# Receiver_SMD.net
KiCad netlist of a schematic drawn in EAGLE
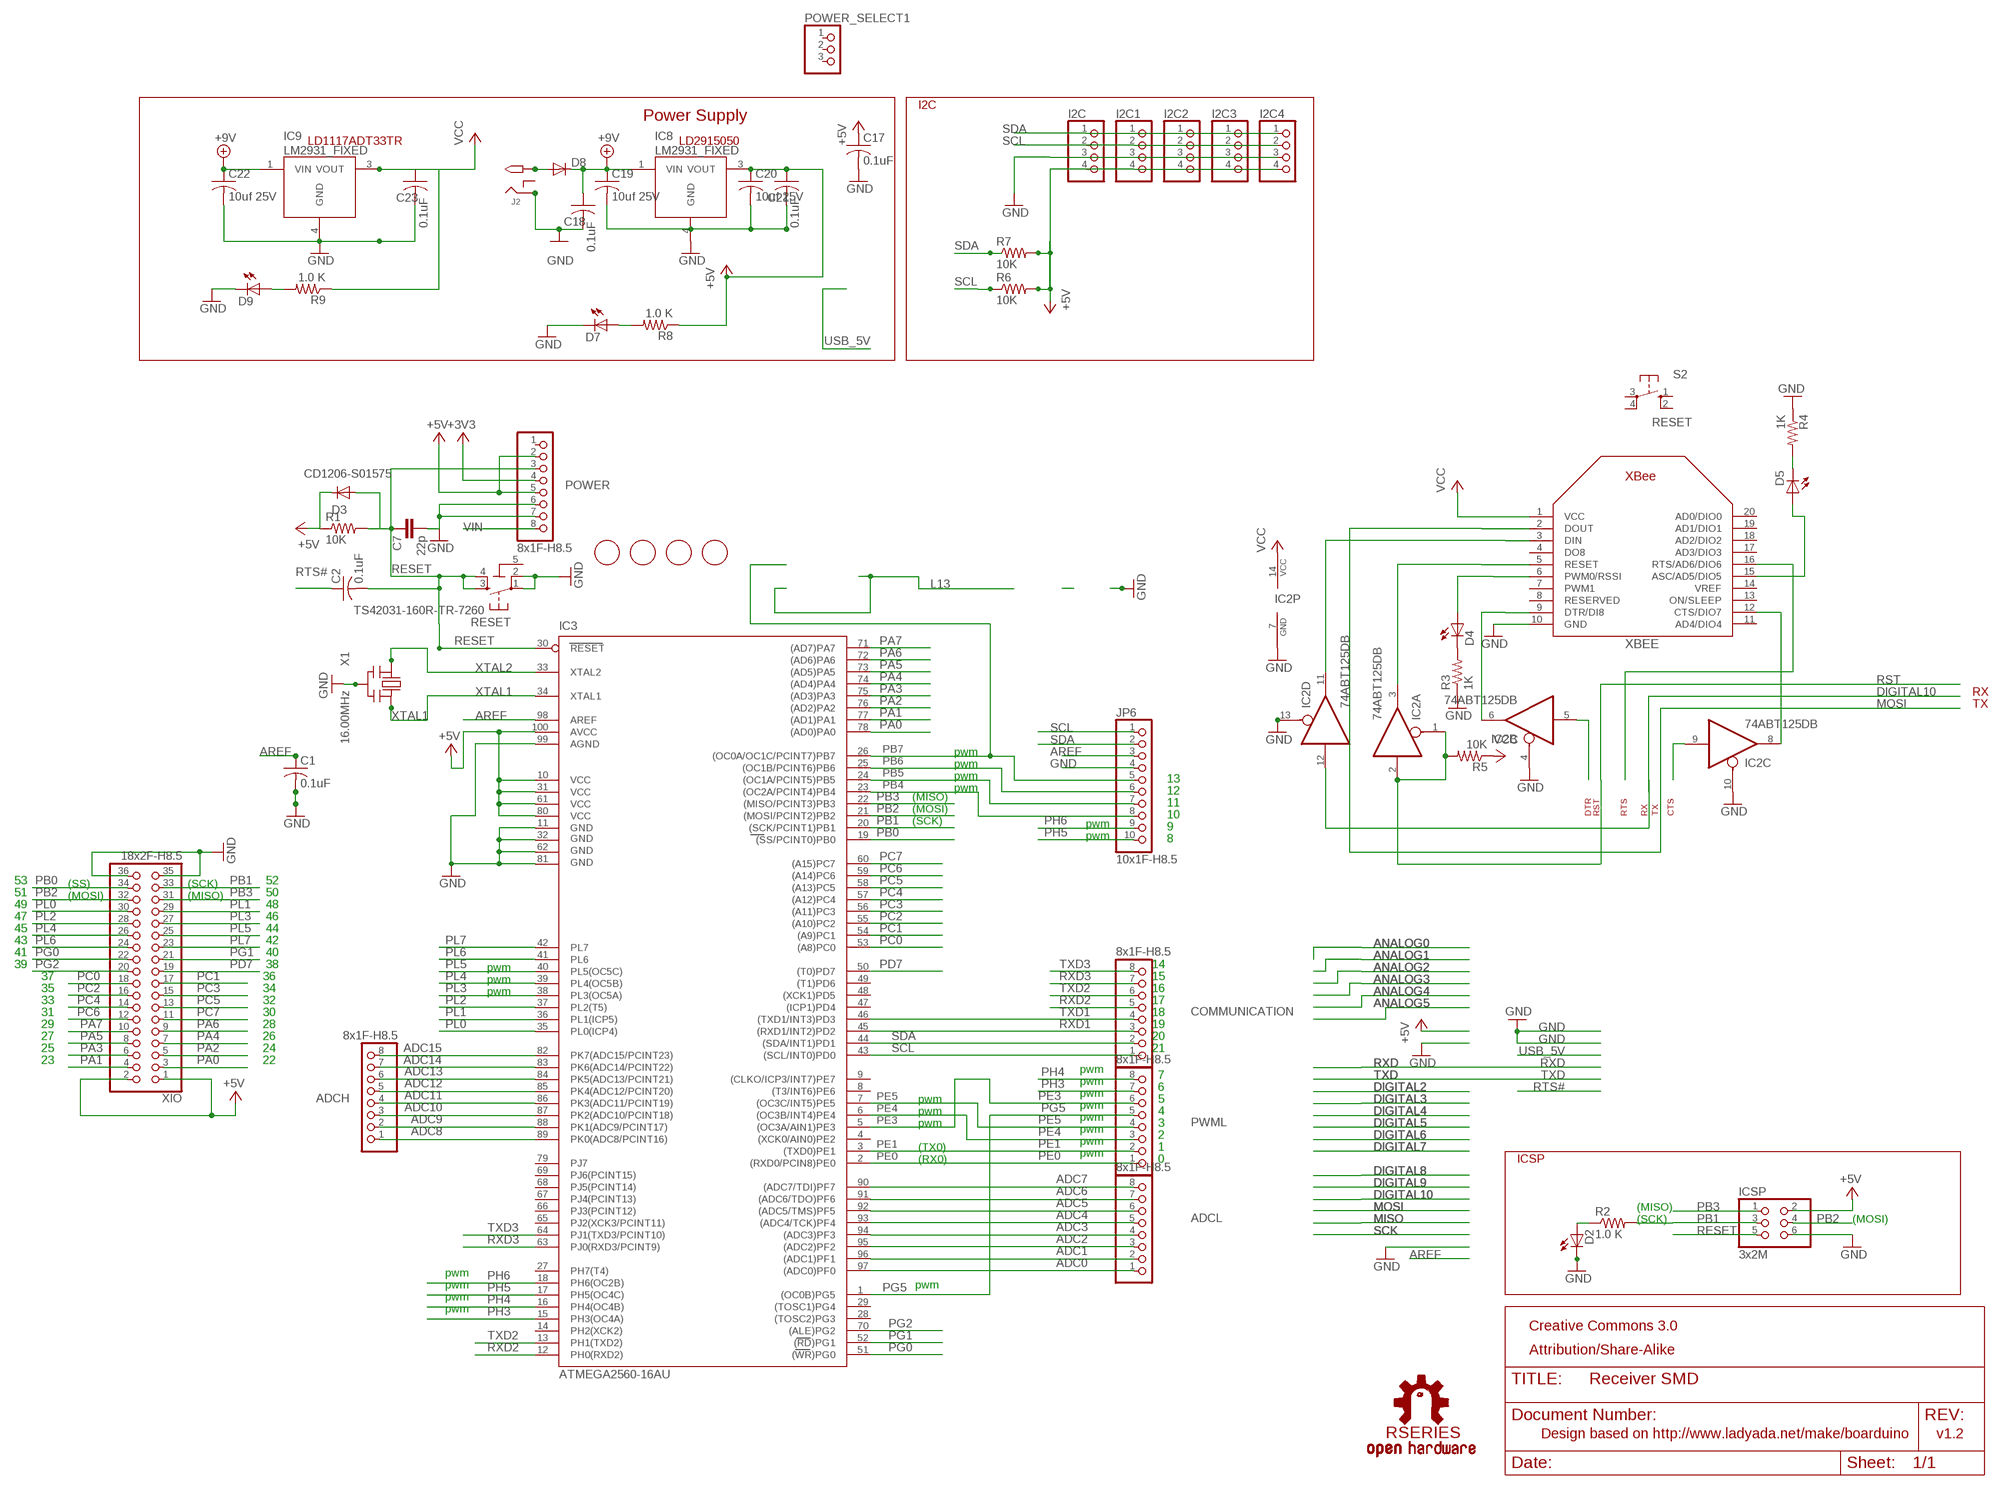
[diagram p0: schematic, sheet 1]

(export (version "E")
  (design (tool "Eeschema 10.0.6"))
  (components
    (comp (ref "ADCH")
      (value "8x1F-H8.5")
      (footprint "eagle-import:1X08")
      (libsource (lib "eagle-import") (part "PINHD-1X8"))
    )
    (comp (ref "ADCL")
      (value "8x1F-H8.5")
      (footprint "eagle-import:1X08")
      (libsource (lib "eagle-import") (part "PINHD-1X8"))
    )
    (comp (ref "C1")
      (value "0.1uF")
      (footprint "eagle-import:C1206K")
      (libsource (lib "eagle-import") (part "C-USC1206K"))
    )
    (comp (ref "C2")
      (value "0.1uF")
      (footprint "eagle-import:C1206K")
      (libsource (lib "eagle-import") (part "C-USC1206K"))
    )
    (comp (ref "C7")
      (value "22p")
      (footprint "eagle-import:C0603-ROUND")
      (libsource (lib "eagle-import") (part "C-EU0603-RND"))
    )
    (comp (ref "C17")
      (value "0.1uF")
      (footprint "eagle-import:C1206K")
      (libsource (lib "eagle-import") (part "C-USC1206K"))
    )
    (comp (ref "C18")
      (value "0.1uF")
      (footprint "eagle-import:C1206K")
      (libsource (lib "eagle-import") (part "C-USC1206K"))
    )
    (comp (ref "C19")
      (value "10uf 25V")
      (footprint "eagle-import:C1206K")
      (libsource (lib "eagle-import") (part "rcl_C-USC1206K"))
    )
    (comp (ref "C20")
      (value "10uf 25V")
      (footprint "eagle-import:C1206K")
      (libsource (lib "eagle-import") (part "rcl_C-USC1206K"))
    )
    (comp (ref "C21")
      (value "0.1uF")
      (footprint "eagle-import:C1206K")
      (libsource (lib "eagle-import") (part "C-USC1206K"))
    )
    (comp (ref "C22")
      (value "10uf 25V")
      (footprint "eagle-import:C1206K")
      (libsource (lib "eagle-import") (part "rcl_C-USC1206K"))
    )
    (comp (ref "C23")
      (value "0.1uF")
      (footprint "eagle-import:C1206K")
      (libsource (lib "eagle-import") (part "C-USC1206K"))
    )
    (comp (ref "COMMUNICATION")
      (value "8x1F-H8.5")
      (footprint "eagle-import:1X08")
      (libsource (lib "eagle-import") (part "PINHD-1X8"))
    )
    (comp (ref "D2")
      (value "RED")
      (footprint "eagle-import:CHIPLED_1206")
      (libsource (lib "eagle-import") (part "LEDCHIPLED_1206"))
    )
    (comp (ref "D3")
      (value "CD1206-S01575")
      (footprint "eagle-import:MINIMELF")
      (libsource (lib "eagle-import") (part "DIODE-MINIMELF"))
    )
    (comp (ref "D4")
      (value "LEDCHIPLED_1206")
      (footprint "eagle-import:CHIPLED_1206")
      (libsource (lib "eagle-import") (part "LEDCHIPLED_1206"))
    )
    (comp (ref "D5")
      (value "LEDCHIPLED_1206")
      (footprint "eagle-import:CHIPLED_1206")
      (libsource (lib "eagle-import") (part "LEDCHIPLED_1206"))
    )
    (comp (ref "D7")
      (value "LEDCHIPLED_1206")
      (footprint "eagle-import:CHIPLED_1206")
      (libsource (lib "eagle-import") (part "LEDCHIPLED_1206"))
    )
    (comp (ref "D8")
      (value "DIODE-SMB")
      (footprint "eagle-import:SMB")
      (libsource (lib "eagle-import") (part "DIODE-SMB"))
    )
    (comp (ref "D9")
      (value "LEDCHIPLED_1206")
      (footprint "eagle-import:CHIPLED_1206")
      (libsource (lib "eagle-import") (part "LEDCHIPLED_1206"))
    )
    (comp (ref "FD1")
      (value "FIDUCIALMOUNT")
      (footprint "eagle-import:FIDUCIA-MOUNT")
      (libsource (lib "eagle-import") (part "FIDUCIALMOUNT"))
    )
    (comp (ref "FD2")
      (value "FIDUCIALMOUNT")
      (footprint "eagle-import:FIDUCIA-MOUNT")
      (libsource (lib "eagle-import") (part "FIDUCIALMOUNT"))
    )
    (comp (ref "FD3")
      (value "FIDUCIALMOUNT")
      (footprint "eagle-import:FIDUCIA-MOUNT")
      (libsource (lib "eagle-import") (part "FIDUCIALMOUNT"))
    )
    (comp (ref "FD4")
      (value "FIDUCIALMOUNT")
      (footprint "eagle-import:FIDUCIA-MOUNT")
      (libsource (lib "eagle-import") (part "FIDUCIALMOUNT"))
    )
    (comp (ref "I2C")
      (value "PINHD-1X4CB")
      (footprint "eagle-import:1X04-CB")
      (libsource (lib "eagle-import") (part "PINHD-1X4CB"))
    )
    (comp (ref "I2C1")
      (value "PINHD-1X4CB")
      (footprint "eagle-import:1X04-CB")
      (libsource (lib "eagle-import") (part "PINHD-1X4CB"))
    )
    (comp (ref "I2C2")
      (value "PINHD-1X4CB")
      (footprint "eagle-import:1X04-CB")
      (libsource (lib "eagle-import") (part "PINHD-1X4CB"))
    )
    (comp (ref "I2C3")
      (value "PINHD-1X4CB")
      (footprint "eagle-import:1X04-CB")
      (libsource (lib "eagle-import") (part "PINHD-1X4CB"))
    )
    (comp (ref "I2C4")
      (value "PINHD-1X4CB")
      (footprint "eagle-import:1X04-CB")
      (libsource (lib "eagle-import") (part "PINHD-1X4CB"))
    )
    (comp (ref "IC2")
      (value "74ABT125DB")
      (footprint "eagle-import:SSOP14")
      (libsource (lib "eagle-import") (part "74125DBABT"))
    )
    (comp (ref "IC3")
      (value "ATMEGA2560-16AU")
      (footprint "eagle-import:TQFP100")
      (libsource (lib "eagle-import") (part "ATMEGA2560AU2560-16"))
    )
    (comp (ref "IC8")
      (value "LM2931_FIXED")
      (footprint "eagle-import:DPAK")
      (libsource (lib "eagle-import") (part "LM2931_FIXED"))
    )
    (comp (ref "IC9")
      (value "LM2931_FIXED")
      (footprint "eagle-import:DPAK")
      (libsource (lib "eagle-import") (part "LM2931_FIXED"))
    )
    (comp (ref "ICSP")
      (value "3x2M")
      (footprint "eagle-import:2X03")
      (libsource (lib "eagle-import") (part "PINHD-2X3"))
    )
    (comp (ref "J2")
      (value "2.1MMJACK")
      (footprint "eagle-import:PJ-102A")
      (libsource (lib "eagle-import") (part "2.1MMJACK"))
    )
    (comp (ref "JP6")
      (value "10x1F-H8.5")
      (footprint "eagle-import:1X10")
      (libsource (lib "eagle-import") (part "PINHD-1X10_ARD"))
    )
    (comp (ref "POWER")
      (value "8x1F-H8.5")
      (footprint "eagle-import:1X08")
      (libsource (lib "eagle-import") (part "PINHD-1X8"))
    )
    (comp (ref "POWER_SELECT1")
      (value "PINHD-1X3")
      (footprint "eagle-import:1X03")
      (libsource (lib "eagle-import") (part "PINHD-1X3"))
    )
    (comp (ref "PWML")
      (value "8x1F-H8.5")
      (footprint "eagle-import:1X08")
      (libsource (lib "eagle-import") (part "PINHD-1X8"))
    )
    (comp (ref "R1")
      (value "10K")
      (footprint "eagle-import:R1206")
      (libsource (lib "eagle-import") (part "rcl-ez_R-US_R1206"))
    )
    (comp (ref "R2")
      (value "1.0 K")
      (footprint "eagle-import:M1206")
      (libsource (lib "eagle-import") (part "R-US_M1206"))
    )
    (comp (ref "R3")
      (value "1K")
      (footprint "eagle-import:R1206")
      (libsource (lib "eagle-import") (part "rcl-ez_R-US_R1206"))
    )
    (comp (ref "R4")
      (value "1K")
      (footprint "eagle-import:R1206")
      (libsource (lib "eagle-import") (part "rcl-ez_R-US_R1206"))
    )
    (comp (ref "R5")
      (value "10K")
      (footprint "eagle-import:R1206")
      (libsource (lib "eagle-import") (part "rcl-ez_R-US_R1206"))
    )
    (comp (ref "R6")
      (value "10K")
      (footprint "eagle-import:R1206")
      (libsource (lib "eagle-import") (part "rcl-ez_R-US_R1206"))
    )
    (comp (ref "R7")
      (value "10K")
      (footprint "eagle-import:R1206")
      (libsource (lib "eagle-import") (part "rcl-ez_R-US_R1206"))
    )
    (comp (ref "R8")
      (value "1.0 K")
      (footprint "eagle-import:M1206")
      (libsource (lib "eagle-import") (part "R-US_M1206"))
    )
    (comp (ref "R9")
      (value "1.0 K")
      (footprint "eagle-import:M1206")
      (libsource (lib "eagle-import") (part "R-US_M1206"))
    )
    (comp (ref "RESET")
      (value "TS42031-160R-TR-7260")
      (footprint "eagle-import:TS42")
      (libsource (lib "eagle-import") (part "TS42"))
    )
    (comp (ref "S2")
      (value "RESET")
      (footprint "eagle-import:B3F-10XX")
      (libsource (lib "eagle-import") (part "10-XX"))
    )
    (comp (ref "U$6")
      (value "RSERIES-OSHW-LOGOMEDIUM")
      (footprint "eagle-import:RSERIES-OSHW-LOGO-MEDIUM")
      (libsource (lib "eagle-import") (part "RSERIES-OSHW-LOGOMEDIUM"))
    )
    (comp (ref "X1")
      (value "16.00MHz")
      (footprint "eagle-import:CERM_OSC")
      (libsource (lib "eagle-import") (part "CERMOSCILL"))
    )
    (comp (ref "XBEE")
      (value "XBEE")
      (footprint "eagle-import:XBEE")
      (libsource (lib "eagle-import") (part "XBEE"))
    )
    (comp (ref "XIO")
      (value "18x2F-H8.5")
      (footprint "eagle-import:2X18")
      (libsource (lib "eagle-import") (part "PINHD-2X18"))
    )
  )
  (nets
    (net (code "1") (name "+3V3") (class "Default")
      (node (ref "POWER") (pin "4") (pinfunction "4_4") (pintype "passive"))
    )
    (net (code "2") (name "+5V") (class "Default")
      (node (ref "C17") (pin "1") (pinfunction "1_1") (pintype "passive"))
      (node (ref "C20") (pin "1") (pinfunction "1_1") (pintype "passive"))
      (node (ref "C21") (pin "1") (pinfunction "1_1") (pintype "passive"))
      (node (ref "D3") (pin "C") (pinfunction "C_C") (pintype "passive"))
      (node (ref "I2C") (pin "4") (pinfunction "4_4") (pintype "passive"))
      (node (ref "I2C1") (pin "4") (pinfunction "4_4") (pintype "passive"))
      (node (ref "I2C2") (pin "4") (pinfunction "4_4") (pintype "passive"))
      (node (ref "I2C3") (pin "4") (pinfunction "4_4") (pintype "passive"))
      (node (ref "I2C4") (pin "4") (pinfunction "4_4") (pintype "passive"))
      (node (ref "IC3") (pin "10") (pinfunction "VCC_10") (pintype "power_in"))
      (node (ref "IC3") (pin "100") (pinfunction "AVCC_100") (pintype "power_in"))
      (node (ref "IC3") (pin "31") (pinfunction "VCC1_31") (pintype "power_in"))
      (node (ref "IC3") (pin "61") (pinfunction "VCC2_61") (pintype "power_in"))
      (node (ref "IC3") (pin "80") (pinfunction "VCC3_80") (pintype "power_in"))
      (node (ref "IC8") (pin "3") (pinfunction "VOUT_3") (pintype "bidirectional"))
      (node (ref "ICSP") (pin "2") (pinfunction "2_2") (pintype "passive"))
      (node (ref "POWER") (pin "2") (pinfunction "2_2") (pintype "passive"))
      (node (ref "POWER") (pin "5") (pinfunction "5_5") (pintype "passive"))
      (node (ref "R1") (pin "1") (pinfunction "1_1") (pintype "passive"))
      (node (ref "R6") (pin "2") (pinfunction "2_2") (pintype "passive"))
      (node (ref "R7") (pin "2") (pinfunction "2_2") (pintype "passive"))
      (node (ref "R8") (pin "1") (pinfunction "1_1") (pintype "passive"))
      (node (ref "XIO") (pin "1") (pinfunction "1_1") (pintype "passive"))
      (node (ref "XIO") (pin "2") (pinfunction "2_2") (pintype "passive"))
    )
    (net (code "3") (name "+9V") (class "Default")
      (node (ref "C18") (pin "1") (pinfunction "1_1") (pintype "passive"))
      (node (ref "C19") (pin "1") (pinfunction "1_1") (pintype "passive"))
      (node (ref "C22") (pin "1") (pinfunction "1_1") (pintype "passive"))
      (node (ref "D8") (pin "C") (pinfunction "C_C") (pintype "passive"))
      (node (ref "IC8") (pin "1") (pinfunction "VIN_1") (pintype "bidirectional"))
      (node (ref "IC9") (pin "1") (pinfunction "VIN_1") (pintype "bidirectional"))
    )
    (net (code "4") (name "/5-GND") (class "Default")
      (node (ref "RESET") (pin "5") (pinfunction "5-GND_5") (pintype "power_in"))
    )
    (net (code "5") (name "/ADC0") (class "Default")
      (node (ref "ADCL") (pin "1") (pinfunction "1_1") (pintype "passive"))
      (node (ref "IC3") (pin "97") (pinfunction "(ADC0)PF0_97") (pintype "bidirectional"))
    )
    (net (code "6") (name "/ADC1") (class "Default")
      (node (ref "ADCL") (pin "2") (pinfunction "2_2") (pintype "passive"))
      (node (ref "IC3") (pin "96") (pinfunction "(ADC1)PF1_96") (pintype "bidirectional"))
    )
    (net (code "7") (name "/ADC2") (class "Default")
      (node (ref "ADCL") (pin "3") (pinfunction "3_3") (pintype "passive"))
      (node (ref "IC3") (pin "95") (pinfunction "(ADC2)PF2_95") (pintype "bidirectional"))
    )
    (net (code "8") (name "/ADC3") (class "Default")
      (node (ref "ADCL") (pin "4") (pinfunction "4_4") (pintype "passive"))
      (node (ref "IC3") (pin "94") (pinfunction "(ADC3)PF3_94") (pintype "bidirectional"))
    )
    (net (code "9") (name "/ADC4") (class "Default")
      (node (ref "ADCL") (pin "5") (pinfunction "5_5") (pintype "passive"))
      (node (ref "IC3") (pin "93") (pinfunction "(ADC4/TCK)PF4_93") (pintype "bidirectional"))
    )
    (net (code "10") (name "/ADC5") (class "Default")
      (node (ref "ADCL") (pin "6") (pinfunction "6_6") (pintype "passive"))
      (node (ref "IC3") (pin "92") (pinfunction "(ADC5/TMS)PF5_92") (pintype "bidirectional"))
    )
    (net (code "11") (name "/ADC6") (class "Default")
      (node (ref "ADCL") (pin "7") (pinfunction "7_7") (pintype "passive"))
      (node (ref "IC3") (pin "91") (pinfunction "(ADC6/TDO)PF6_91") (pintype "bidirectional"))
    )
    (net (code "12") (name "/ADC7") (class "Default")
      (node (ref "ADCL") (pin "8") (pinfunction "8_8") (pintype "passive"))
      (node (ref "IC3") (pin "90") (pinfunction "(ADC7/TDI)PF7_90") (pintype "bidirectional"))
    )
    (net (code "13") (name "/ADC8") (class "Default")
      (node (ref "ADCH") (pin "1") (pinfunction "1_1") (pintype "passive"))
      (node (ref "IC3") (pin "89") (pinfunction "PK0(ADC8/PCINT16)_89") (pintype "bidirectional"))
    )
    (net (code "14") (name "/ADC9") (class "Default")
      (node (ref "ADCH") (pin "2") (pinfunction "2_2") (pintype "passive"))
      (node (ref "IC3") (pin "88") (pinfunction "PK1(ADC9/PCINT17)_88") (pintype "bidirectional"))
    )
    (net (code "15") (name "/ADC10") (class "Default")
      (node (ref "ADCH") (pin "3") (pinfunction "3_3") (pintype "passive"))
      (node (ref "IC3") (pin "87") (pinfunction "PK2(ADC10/PCINT18)_87") (pintype "bidirectional"))
    )
    (net (code "16") (name "/ADC11") (class "Default")
      (node (ref "ADCH") (pin "4") (pinfunction "4_4") (pintype "passive"))
      (node (ref "IC3") (pin "86") (pinfunction "PK3(ADC11/PCINT19)_86") (pintype "bidirectional"))
    )
    (net (code "17") (name "/ADC12") (class "Default")
      (node (ref "ADCH") (pin "5") (pinfunction "5_5") (pintype "passive"))
      (node (ref "IC3") (pin "85") (pinfunction "PK4(ADC12/PCINT20)_85") (pintype "bidirectional"))
    )
    (net (code "18") (name "/ADC13") (class "Default")
      (node (ref "ADCH") (pin "6") (pinfunction "6_6") (pintype "passive"))
      (node (ref "IC3") (pin "84") (pinfunction "PK5(ADC13/PCINT21)_84") (pintype "bidirectional"))
    )
    (net (code "19") (name "/ADC14") (class "Default")
      (node (ref "ADCH") (pin "7") (pinfunction "7_7") (pintype "passive"))
      (node (ref "IC3") (pin "83") (pinfunction "PK6(ADC14/PCINT22)_83") (pintype "bidirectional"))
    )
    (net (code "20") (name "/ADC15") (class "Default")
      (node (ref "ADCH") (pin "8") (pinfunction "8_8") (pintype "passive"))
      (node (ref "IC3") (pin "82") (pinfunction "PK7(ADC15/PCINT23)_82") (pintype "bidirectional"))
    )
    (net (code "27") (name "/AREF") (class "Default")
      (node (ref "C1") (pin "1") (pinfunction "1_1") (pintype "passive"))
      (node (ref "IC3") (pin "98") (pinfunction "AREF_98") (pintype "bidirectional"))
      (node (ref "JP6") (pin "3") (pinfunction "3_3") (pintype "passive"))
    )
    (net (code "36") (name "/DIGITAL10") (class "Default")
      (node (ref "IC2") (pin "12") (pinfunction "I_12") (pintype "input"))
    )
    (net (code "39") (name "/MOSI") (class "Default")
      (node (ref "XBEE") (pin "2") (pinfunction "DOUT_2") (pintype "output"))
    )
    (net (code "40") (name "/PA0") (class "Default")
      (node (ref "IC3") (pin "78") (pinfunction "(AD0)PA0_78") (pintype "bidirectional"))
      (node (ref "XIO") (pin "3") (pinfunction "3_3") (pintype "passive"))
    )
    (net (code "41") (name "/PA1") (class "Default")
      (node (ref "IC3") (pin "77") (pinfunction "(AD1)PA1_77") (pintype "bidirectional"))
      (node (ref "XIO") (pin "4") (pinfunction "4_4") (pintype "passive"))
    )
    (net (code "42") (name "/PA2") (class "Default")
      (node (ref "IC3") (pin "76") (pinfunction "(AD2)PA2_76") (pintype "bidirectional"))
      (node (ref "XIO") (pin "5") (pinfunction "5_5") (pintype "passive"))
    )
    (net (code "43") (name "/PA3") (class "Default")
      (node (ref "IC3") (pin "75") (pinfunction "(AD3)PA3_75") (pintype "bidirectional"))
      (node (ref "XIO") (pin "6") (pinfunction "6_6") (pintype "passive"))
    )
    (net (code "44") (name "/PA4") (class "Default")
      (node (ref "IC3") (pin "74") (pinfunction "(AD4)PA4_74") (pintype "bidirectional"))
      (node (ref "XIO") (pin "7") (pinfunction "7_7") (pintype "passive"))
    )
    (net (code "45") (name "/PA5") (class "Default")
      (node (ref "IC3") (pin "73") (pinfunction "(AD5)PA5_73") (pintype "bidirectional"))
      (node (ref "XIO") (pin "8") (pinfunction "8_8") (pintype "passive"))
    )
    (net (code "46") (name "/PA6") (class "Default")
      (node (ref "IC3") (pin "72") (pinfunction "(AD6)PA6_72") (pintype "bidirectional"))
      (node (ref "XIO") (pin "9") (pinfunction "9_9") (pintype "passive"))
    )
    (net (code "47") (name "/PA7") (class "Default")
      (node (ref "IC3") (pin "71") (pinfunction "(AD7)PA7_71") (pintype "bidirectional"))
      (node (ref "XIO") (pin "10") (pinfunction "10_10") (pintype "passive"))
    )
    (net (code "48") (name "/PB0") (class "Default")
      (node (ref "IC3") (pin "19") (pinfunction "(SS/PCINT0)PB0_19") (pintype "bidirectional"))
      (node (ref "XIO") (pin "34") (pinfunction "34_34") (pintype "passive"))
    )
    (net (code "49") (name "/PB1") (class "Default")
      (node (ref "IC3") (pin "20") (pinfunction "(SCK/PCINT1)PB1_20") (pintype "bidirectional"))
      (node (ref "ICSP") (pin "3") (pinfunction "3_3") (pintype "passive"))
      (node (ref "R2") (pin "2") (pinfunction "2_2") (pintype "passive"))
      (node (ref "XIO") (pin "33") (pinfunction "33_33") (pintype "passive"))
    )
    (net (code "50") (name "/PB2") (class "Default")
      (node (ref "IC3") (pin "21") (pinfunction "(MOSI/PCINT2)PB2_21") (pintype "bidirectional"))
      (node (ref "ICSP") (pin "4") (pinfunction "4_4") (pintype "passive"))
      (node (ref "XIO") (pin "32") (pinfunction "32_32") (pintype "passive"))
    )
    (net (code "51") (name "/PB3") (class "Default")
      (node (ref "IC3") (pin "22") (pinfunction "(MISO/PCINT3)PB3_22") (pintype "bidirectional"))
      (node (ref "ICSP") (pin "1") (pinfunction "1_1") (pintype "passive"))
      (node (ref "XIO") (pin "31") (pinfunction "31_31") (pintype "passive"))
    )
    (net (code "52") (name "/PB4") (class "Default")
      (node (ref "IC3") (pin "23") (pinfunction "(OC2A/PCINT4)PB4_23") (pintype "bidirectional"))
      (node (ref "JP6") (pin "8") (pinfunction "8_8") (pintype "passive"))
    )
    (net (code "53") (name "/PB5") (class "Default")
      (node (ref "IC3") (pin "24") (pinfunction "(OC1A/PCINT5)PB5_24") (pintype "bidirectional"))
      (node (ref "JP6") (pin "7") (pinfunction "7_7") (pintype "passive"))
    )
    (net (code "54") (name "/PB6") (class "Default")
      (node (ref "IC3") (pin "25") (pinfunction "(OC1B/PCINT6)PB6_25") (pintype "bidirectional"))
      (node (ref "JP6") (pin "6") (pinfunction "6_6") (pintype "passive"))
    )
    (net (code "55") (name "/PB7") (class "Default")
      (node (ref "IC3") (pin "26") (pinfunction "(OC0A/OC1C/PCINT7)PB7_26") (pintype "bidirectional"))
      (node (ref "JP6") (pin "5") (pinfunction "5_5") (pintype "passive"))
    )
    (net (code "56") (name "/PC0") (class "Default")
      (node (ref "IC3") (pin "53") (pinfunction "(A8)PC0_53") (pintype "bidirectional"))
      (node (ref "XIO") (pin "18") (pinfunction "18_18") (pintype "passive"))
    )
    (net (code "57") (name "/PC1") (class "Default")
      (node (ref "IC3") (pin "54") (pinfunction "(A9)PC1_54") (pintype "bidirectional"))
      (node (ref "XIO") (pin "17") (pinfunction "17_17") (pintype "passive"))
    )
    (net (code "58") (name "/PC2") (class "Default")
      (node (ref "IC3") (pin "55") (pinfunction "(A10)PC2_55") (pintype "bidirectional"))
      (node (ref "XIO") (pin "16") (pinfunction "16_16") (pintype "passive"))
    )
    (net (code "59") (name "/PC3") (class "Default")
      (node (ref "IC3") (pin "56") (pinfunction "(A11)PC3_56") (pintype "bidirectional"))
      (node (ref "XIO") (pin "15") (pinfunction "15_15") (pintype "passive"))
    )
    (net (code "60") (name "/PC4") (class "Default")
      (node (ref "IC3") (pin "57") (pinfunction "(A12)PC4_57") (pintype "bidirectional"))
      (node (ref "XIO") (pin "14") (pinfunction "14_14") (pintype "passive"))
    )
    (net (code "61") (name "/PC5") (class "Default")
      (node (ref "IC3") (pin "58") (pinfunction "(A13)PC5_58") (pintype "bidirectional"))
      (node (ref "XIO") (pin "13") (pinfunction "13_13") (pintype "passive"))
    )
    (net (code "62") (name "/PC6") (class "Default")
      (node (ref "IC3") (pin "59") (pinfunction "(A14)PC6_59") (pintype "bidirectional"))
      (node (ref "XIO") (pin "12") (pinfunction "12_12") (pintype "passive"))
    )
    (net (code "63") (name "/PC7") (class "Default")
      (node (ref "IC3") (pin "60") (pinfunction "(A15)PC7_60") (pintype "bidirectional"))
      (node (ref "XIO") (pin "11") (pinfunction "11_11") (pintype "passive"))
    )
    (net (code "64") (name "/PD7") (class "Default")
      (node (ref "IC3") (pin "50") (pinfunction "(T0)PD7_50") (pintype "bidirectional"))
      (node (ref "XIO") (pin "19") (pinfunction "19_19") (pintype "passive"))
    )
    (net (code "65") (name "/PE0") (class "Default")
      (node (ref "IC3") (pin "2") (pinfunction "(RXD0/PCIN8)PE0_2") (pintype "bidirectional"))
      (node (ref "PWML") (pin "1") (pinfunction "1_1") (pintype "passive"))
    )
    (net (code "66") (name "/PE1") (class "Default")
      (node (ref "IC3") (pin "3") (pinfunction "(TXD0)PE1_3") (pintype "bidirectional"))
      (node (ref "PWML") (pin "2") (pinfunction "2_2") (pintype "passive"))
    )
    (net (code "67") (name "/PE3") (class "Default")
      (node (ref "IC3") (pin "5") (pinfunction "(OC3A/AIN1)PE3_5") (pintype "bidirectional"))
      (node (ref "PWML") (pin "6") (pinfunction "6_6") (pintype "passive"))
    )
    (net (code "68") (name "/PE4") (class "Default")
      (node (ref "IC3") (pin "6") (pinfunction "(OC3B/INT4)PE4_6") (pintype "bidirectional"))
      (node (ref "PWML") (pin "3") (pinfunction "3_3") (pintype "passive"))
    )
    (net (code "69") (name "/PE5") (class "Default")
      (node (ref "IC3") (pin "7") (pinfunction "(OC3C/INT5)PE5_7") (pintype "bidirectional"))
      (node (ref "PWML") (pin "4") (pinfunction "4_4") (pintype "passive"))
    )
    (net (code "70") (name "/PG0") (class "Default")
      (node (ref "IC3") (pin "51") (pinfunction "(WR)PG0_51") (pintype "bidirectional"))
      (node (ref "XIO") (pin "22") (pinfunction "22_22") (pintype "passive"))
    )
    (net (code "71") (name "/PG1") (class "Default")
      (node (ref "IC3") (pin "52") (pinfunction "(RD)PG1_52") (pintype "bidirectional"))
      (node (ref "XIO") (pin "21") (pinfunction "21_21") (pintype "passive"))
    )
    (net (code "72") (name "/PG2") (class "Default")
      (node (ref "IC3") (pin "70") (pinfunction "(ALE)PG2_70") (pintype "bidirectional"))
      (node (ref "XIO") (pin "20") (pinfunction "20_20") (pintype "passive"))
    )
    (net (code "73") (name "/PG5") (class "Default")
      (node (ref "IC3") (pin "1") (pinfunction "(OC0B)PG5_1") (pintype "bidirectional"))
      (node (ref "PWML") (pin "5") (pinfunction "5_5") (pintype "passive"))
    )
    (net (code "74") (name "/PH3") (class "Default")
      (node (ref "IC3") (pin "15") (pinfunction "PH3(OC4A)_15") (pintype "bidirectional"))
      (node (ref "PWML") (pin "7") (pinfunction "7_7") (pintype "passive"))
    )
    (net (code "75") (name "/PH4") (class "Default")
      (node (ref "IC3") (pin "16") (pinfunction "PH4(OC4B)_16") (pintype "bidirectional"))
      (node (ref "PWML") (pin "8") (pinfunction "8_8") (pintype "passive"))
    )
    (net (code "76") (name "/PH5") (class "Default")
      (node (ref "IC3") (pin "17") (pinfunction "PH5(OC4C)_17") (pintype "bidirectional"))
      (node (ref "JP6") (pin "10") (pinfunction "10_10") (pintype "passive"))
    )
    (net (code "77") (name "/PH6") (class "Default")
      (node (ref "IC3") (pin "18") (pinfunction "PH6(OC2B)_18") (pintype "bidirectional"))
      (node (ref "JP6") (pin "9") (pinfunction "9_9") (pintype "passive"))
    )
    (net (code "78") (name "/PL0") (class "Default")
      (node (ref "IC3") (pin "35") (pinfunction "PL0(ICP4)_35") (pintype "bidirectional"))
      (node (ref "XIO") (pin "30") (pinfunction "30_30") (pintype "passive"))
    )
    (net (code "79") (name "/PL1") (class "Default")
      (node (ref "IC3") (pin "36") (pinfunction "PL1(ICP5)_36") (pintype "bidirectional"))
      (node (ref "XIO") (pin "29") (pinfunction "29_29") (pintype "passive"))
    )
    (net (code "80") (name "/PL2") (class "Default")
      (node (ref "IC3") (pin "37") (pinfunction "PL2(T5)_37") (pintype "bidirectional"))
      (node (ref "XIO") (pin "28") (pinfunction "28_28") (pintype "passive"))
    )
    (net (code "81") (name "/PL3") (class "Default")
      (node (ref "IC3") (pin "38") (pinfunction "PL3(OC5A)_38") (pintype "bidirectional"))
      (node (ref "XIO") (pin "27") (pinfunction "27_27") (pintype "passive"))
    )
    (net (code "82") (name "/PL4") (class "Default")
      (node (ref "IC3") (pin "39") (pinfunction "PL4(OC5B)_39") (pintype "bidirectional"))
      (node (ref "XIO") (pin "26") (pinfunction "26_26") (pintype "passive"))
    )
    (net (code "83") (name "/PL5") (class "Default")
      (node (ref "IC3") (pin "40") (pinfunction "PL5(OC5C)_40") (pintype "bidirectional"))
      (node (ref "XIO") (pin "25") (pinfunction "25_25") (pintype "passive"))
    )
    (net (code "84") (name "/PL6") (class "Default")
      (node (ref "IC3") (pin "41") (pinfunction "PL6_41") (pintype "bidirectional"))
      (node (ref "XIO") (pin "24") (pinfunction "24_24") (pintype "passive"))
    )
    (net (code "85") (name "/PL7") (class "Default")
      (node (ref "IC3") (pin "42") (pinfunction "PL7_42") (pintype "bidirectional"))
      (node (ref "XIO") (pin "23") (pinfunction "23_23") (pintype "passive"))
    )
    (net (code "86") (name "/RESET") (class "Default")
      (node (ref "C2") (pin "2") (pinfunction "2_2") (pintype "passive"))
      (node (ref "C7") (pin "1") (pinfunction "1_1") (pintype "passive"))
      (node (ref "D3") (pin "A") (pinfunction "A_A") (pintype "passive"))
      (node (ref "IC3") (pin "30") (pinfunction "RESET_30") (pintype "input"))
      (node (ref "ICSP") (pin "5") (pinfunction "5_5") (pintype "passive"))
      (node (ref "POWER") (pin "3") (pinfunction "3_3") (pintype "passive"))
      (node (ref "R1") (pin "2") (pinfunction "2_2") (pintype "passive"))
      (node (ref "RESET") (pin "3") (pinfunction "3_3") (pintype "passive"))
      (node (ref "RESET") (pin "4") (pinfunction "4_4") (pintype "passive"))
    )
    (net (code "87") (name "/RST") (class "Default")
      (node (ref "IC2") (pin "1") (pinfunction "OE_1") (pintype "input"))
      (node (ref "IC2") (pin "2") (pinfunction "I_2") (pintype "input"))
      (node (ref "R5") (pin "2") (pinfunction "2_2") (pintype "passive"))
    )
    (net (code "88") (name "/RTS#") (class "Default")
      (node (ref "C2") (pin "1") (pinfunction "1_1") (pintype "passive"))
    )
    (net (code "90") (name "/RXD1") (class "Default")
      (node (ref "COMMUNICATION") (pin "3") (pinfunction "3_3") (pintype "passive"))
      (node (ref "IC3") (pin "45") (pinfunction "(RXD1/INT2)PD2_45") (pintype "bidirectional"))
    )
    (net (code "91") (name "/RXD2") (class "Default")
      (node (ref "COMMUNICATION") (pin "5") (pinfunction "5_5") (pintype "passive"))
      (node (ref "IC3") (pin "12") (pinfunction "PH0(RXD2)_12") (pintype "bidirectional"))
    )
    (net (code "92") (name "/RXD3") (class "Default")
      (node (ref "COMMUNICATION") (pin "7") (pinfunction "7_7") (pintype "passive"))
      (node (ref "IC3") (pin "63") (pinfunction "PJ0(RXD3/PCINT9)_63") (pintype "bidirectional"))
    )
    (net (code "94") (name "/SCL") (class "Default")
      (node (ref "COMMUNICATION") (pin "1") (pinfunction "1_1") (pintype "passive"))
      (node (ref "I2C") (pin "2") (pinfunction "2_2") (pintype "passive"))
      (node (ref "I2C1") (pin "2") (pinfunction "2_2") (pintype "passive"))
      (node (ref "I2C2") (pin "2") (pinfunction "2_2") (pintype "passive"))
      (node (ref "I2C3") (pin "2") (pinfunction "2_2") (pintype "passive"))
      (node (ref "I2C4") (pin "2") (pinfunction "2_2") (pintype "passive"))
      (node (ref "IC3") (pin "43") (pinfunction "(SCL/INT0)PD0_43") (pintype "bidirectional"))
      (node (ref "JP6") (pin "1") (pinfunction "1_1") (pintype "passive"))
      (node (ref "R6") (pin "1") (pinfunction "1_1") (pintype "passive"))
    )
    (net (code "95") (name "/SDA") (class "Default")
      (node (ref "COMMUNICATION") (pin "2") (pinfunction "2_2") (pintype "passive"))
      (node (ref "I2C") (pin "1") (pinfunction "1_1") (pintype "passive"))
      (node (ref "I2C1") (pin "1") (pinfunction "1_1") (pintype "passive"))
      (node (ref "I2C2") (pin "1") (pinfunction "1_1") (pintype "passive"))
      (node (ref "I2C3") (pin "1") (pinfunction "1_1") (pintype "passive"))
      (node (ref "I2C4") (pin "1") (pinfunction "1_1") (pintype "passive"))
      (node (ref "IC3") (pin "44") (pinfunction "(SDA/INT1)PD1_44") (pintype "bidirectional"))
      (node (ref "JP6") (pin "2") (pinfunction "2_2") (pintype "passive"))
      (node (ref "R7") (pin "1") (pinfunction "1_1") (pintype "passive"))
    )
    (net (code "97") (name "/TXD1") (class "Default")
      (node (ref "COMMUNICATION") (pin "4") (pinfunction "4_4") (pintype "passive"))
      (node (ref "IC3") (pin "46") (pinfunction "(TXD1/INT3)PD3_46") (pintype "bidirectional"))
    )
    (net (code "98") (name "/TXD2") (class "Default")
      (node (ref "COMMUNICATION") (pin "6") (pinfunction "6_6") (pintype "passive"))
      (node (ref "IC3") (pin "13") (pinfunction "PH1(TXD2)_13") (pintype "bidirectional"))
    )
    (net (code "99") (name "/TXD3") (class "Default")
      (node (ref "COMMUNICATION") (pin "8") (pinfunction "8_8") (pintype "passive"))
      (node (ref "IC3") (pin "64") (pinfunction "PJ1(TXD3/PCINT10)_64") (pintype "bidirectional"))
    )
    (net (code "101") (name "/VIN") (class "Default")
      (node (ref "POWER") (pin "8") (pinfunction "8_8") (pintype "passive"))
    )
    (net (code "102") (name "/XTAL1") (class "Default")
      (node (ref "IC3") (pin "34") (pinfunction "XTAL1_34") (pintype "input"))
      (node (ref "X1") (pin "P$3") (pinfunction "OUT_P$3") (pintype "bidirectional"))
    )
    (net (code "103") (name "/XTAL2") (class "Default")
      (node (ref "IC3") (pin "33") (pinfunction "XTAL2_33") (pintype "output"))
      (node (ref "X1") (pin "P$1") (pinfunction "IN_P$1") (pintype "bidirectional"))
    )
    (net (code "104") (name "GND") (class "Default")
      (node (ref "C1") (pin "2") (pinfunction "2_2") (pintype "passive"))
      (node (ref "C17") (pin "2") (pinfunction "2_2") (pintype "passive"))
      (node (ref "C18") (pin "2") (pinfunction "2_2") (pintype "passive"))
      (node (ref "C22") (pin "2") (pinfunction "2_2") (pintype "passive"))
      (node (ref "C23") (pin "2") (pinfunction "2_2") (pintype "passive"))
      (node (ref "C7") (pin "2") (pinfunction "2_2") (pintype "passive"))
      (node (ref "D2") (pin "C") (pinfunction "C_C") (pintype "passive"))
      (node (ref "D7") (pin "C") (pinfunction "C_C") (pintype "passive"))
      (node (ref "D9") (pin "C") (pinfunction "C_C") (pintype "passive"))
      (node (ref "I2C") (pin "3") (pinfunction "3_3") (pintype "passive"))
      (node (ref "I2C1") (pin "3") (pinfunction "3_3") (pintype "passive"))
      (node (ref "I2C2") (pin "3") (pinfunction "3_3") (pintype "passive"))
      (node (ref "I2C3") (pin "3") (pinfunction "3_3") (pintype "passive"))
      (node (ref "I2C4") (pin "3") (pinfunction "3_3") (pintype "passive"))
      (node (ref "IC2") (pin "10") (pinfunction "OE_10") (pintype "input"))
      (node (ref "IC2") (pin "13") (pinfunction "OE_13") (pintype "input"))
      (node (ref "IC2") (pin "4") (pinfunction "OE_4") (pintype "input"))
      (node (ref "IC2") (pin "7") (pinfunction "GND_7") (pintype "power_in"))
      (node (ref "IC3") (pin "11") (pinfunction "GND_11") (pintype "power_in"))
      (node (ref "IC3") (pin "32") (pinfunction "GND1_32") (pintype "power_in"))
      (node (ref "IC3") (pin "62") (pinfunction "GND2_62") (pintype "power_in"))
      (node (ref "IC3") (pin "81") (pinfunction "GND3_81") (pintype "power_in"))
      (node (ref "IC3") (pin "99") (pinfunction "AGND_99") (pintype "power_in"))
      (node (ref "IC8") (pin "4") (pinfunction "GND_4") (pintype "bidirectional"))
      (node (ref "IC9") (pin "4") (pinfunction "GND_4") (pintype "bidirectional"))
      (node (ref "ICSP") (pin "6") (pinfunction "6_6") (pintype "passive"))
      (node (ref "J2") (pin "RING") (pinfunction "RING_RING") (pintype "bidirectional"))
      (node (ref "JP6") (pin "4") (pinfunction "4_4") (pintype "passive"))
      (node (ref "POWER") (pin "6") (pinfunction "6_6") (pintype "passive"))
      (node (ref "POWER") (pin "7") (pinfunction "7_7") (pintype "passive"))
      (node (ref "R3") (pin "1") (pinfunction "1_1") (pintype "passive"))
      (node (ref "R4") (pin "1") (pinfunction "1_1") (pintype "passive"))
      (node (ref "RESET") (pin "1") (pinfunction "1_1") (pintype "passive"))
      (node (ref "RESET") (pin "2") (pinfunction "2_2") (pintype "passive"))
      (node (ref "X1") (pin "P$2") (pinfunction "GND_P$2") (pintype "bidirectional"))
      (node (ref "XBEE") (pin "10") (pinfunction "GND_10") (pintype "power_in"))
      (node (ref "XIO") (pin "35") (pinfunction "35_35") (pintype "passive"))
      (node (ref "XIO") (pin "36") (pinfunction "36_36") (pintype "passive"))
    )
    (net (code "105") (name "Net-(C19-Pad2)") (class "Default")
      (node (ref "C19") (pin "2") (pinfunction "2_2") (pintype "passive"))
      (node (ref "C20") (pin "2") (pinfunction "2_2") (pintype "passive"))
      (node (ref "C21") (pin "2") (pinfunction "2_2") (pintype "passive"))
    )
    (net (code "106") (name "Net-(D2-PadA)") (class "Default")
      (node (ref "D2") (pin "A") (pinfunction "A_A") (pintype "passive"))
      (node (ref "R2") (pin "1") (pinfunction "1_1") (pintype "passive"))
    )
    (net (code "107") (name "Net-(D4-PadC)") (class "Default")
      (node (ref "D4") (pin "C") (pinfunction "C_C") (pintype "passive"))
      (node (ref "R3") (pin "2") (pinfunction "2_2") (pintype "passive"))
    )
    (net (code "108") (name "Net-(D5-PadC)") (class "Default")
      (node (ref "D5") (pin "C") (pinfunction "C_C") (pintype "passive"))
      (node (ref "R4") (pin "2") (pinfunction "2_2") (pintype "passive"))
    )
    (net (code "109") (name "Net-(D7-PadA)") (class "Default")
      (node (ref "D7") (pin "A") (pinfunction "A_A") (pintype "passive"))
      (node (ref "R8") (pin "2") (pinfunction "2_2") (pintype "passive"))
    )
    (net (code "110") (name "Net-(D8-PadA)") (class "Default")
      (node (ref "D8") (pin "A") (pinfunction "A_A") (pintype "passive"))
      (node (ref "J2") (pin "TIP") (pinfunction "TIP_TIP") (pintype "bidirectional"))
    )
    (net (code "111") (name "Net-(D9-PadA)") (class "Default")
      (node (ref "D9") (pin "A") (pinfunction "A_A") (pintype "passive"))
      (node (ref "R9") (pin "2") (pinfunction "2_2") (pintype "passive"))
    )
    (net (code "112") (name "Net-(IC2A-O)") (class "Default")
      (node (ref "IC2") (pin "3") (pinfunction "O_3") (pintype "tri_state"))
      (node (ref "XBEE") (pin "5") (pinfunction "RESET_5") (pintype "input"))
    )
    (net (code "113") (name "Net-(IC2B-O)") (class "Default")
      (node (ref "IC2") (pin "6") (pinfunction "O_6") (pintype "tri_state"))
      (node (ref "XBEE") (pin "9") (pinfunction "DTR/DI8_9") (pintype "input"))
    )
    (net (code "114") (name "Net-(IC2C-O)") (class "Default")
      (node (ref "IC2") (pin "8") (pinfunction "O_8") (pintype "tri_state"))
      (node (ref "XBEE") (pin "12") (pinfunction "CTS/DIO7_12") (pintype "bidirectional"))
    )
    (net (code "115") (name "Net-(IC2D-O)") (class "Default")
      (node (ref "IC2") (pin "11") (pinfunction "O_11") (pintype "tri_state"))
      (node (ref "XBEE") (pin "3") (pinfunction "DIN_3") (pintype "input"))
    )
    (net (code "116") (name "Net-(XBEE-ASC{slash}AD5{slash}DIO5)") (class "Default")
      (node (ref "D5") (pin "A") (pinfunction "A_A") (pintype "passive"))
      (node (ref "XBEE") (pin "15") (pinfunction "ASC/AD5/DIO5_15") (pintype "bidirectional"))
    )
    (net (code "117") (name "Net-(XBEE-PWM0{slash}RSSI)") (class "Default")
      (node (ref "D4") (pin "A") (pinfunction "A_A") (pintype "passive"))
      (node (ref "XBEE") (pin "6") (pinfunction "PWM0/RSSI_6") (pintype "output"))
    )
    (net (code "118") (name "VCC") (class "Default")
      (node (ref "C23") (pin "1") (pinfunction "1_1") (pintype "passive"))
      (node (ref "IC2") (pin "14") (pinfunction "VCC_14") (pintype "power_in"))
      (node (ref "IC9") (pin "3") (pinfunction "VOUT_3") (pintype "bidirectional"))
      (node (ref "R5") (pin "1") (pinfunction "1_1") (pintype "passive"))
      (node (ref "R9") (pin "1") (pinfunction "1_1") (pintype "passive"))
      (node (ref "XBEE") (pin "1") (pinfunction "VCC_1") (pintype "power_in"))
    )
    (net (code "119") (name "unconnected-(IC2B-I-Pad5)") (class "Default")
      (node (ref "IC2") (pin "5") (pinfunction "I_5") (pintype "input"))
    )
    (net (code "120") (name "unconnected-(IC2C-I-Pad9)") (class "Default")
      (node (ref "IC2") (pin "9") (pinfunction "I_9") (pintype "input"))
    )
    (net (code "121") (name "unconnected-(IC3-(CLKO{slash}ICP3{slash}INT7)PE7-Pad9)") (class "Default")
      (node (ref "IC3") (pin "9") (pinfunction "(CLKO/ICP3/INT7)PE7_9") (pintype "bidirectional"))
    )
    (net (code "122") (name "unconnected-(IC3-(ICP1)PD4-Pad47)") (class "Default")
      (node (ref "IC3") (pin "47") (pinfunction "(ICP1)PD4_47") (pintype "bidirectional"))
    )
    (net (code "123") (name "unconnected-(IC3-(T1)PD6-Pad49)") (class "Default")
      (node (ref "IC3") (pin "49") (pinfunction "(T1)PD6_49") (pintype "bidirectional"))
    )
    (net (code "124") (name "unconnected-(IC3-(T3{slash}INT6)PE6-Pad8)") (class "Default")
      (node (ref "IC3") (pin "8") (pinfunction "(T3/INT6)PE6_8") (pintype "bidirectional"))
    )
    (net (code "125") (name "unconnected-(IC3-(TOSC1)PG4-Pad29)") (class "Default")
      (node (ref "IC3") (pin "29") (pinfunction "(TOSC1)PG4_29") (pintype "bidirectional"))
    )
    (net (code "126") (name "unconnected-(IC3-(TOSC2)PG3-Pad28)") (class "Default")
      (node (ref "IC3") (pin "28") (pinfunction "(TOSC2)PG3_28") (pintype "bidirectional"))
    )
    (net (code "127") (name "unconnected-(IC3-(XCK0{slash}AIN0)PE2-Pad4)") (class "Default")
      (node (ref "IC3") (pin "4") (pinfunction "(XCK0/AIN0)PE2_4") (pintype "bidirectional"))
    )
    (net (code "128") (name "unconnected-(IC3-(XCK1)PD5-Pad48)") (class "Default")
      (node (ref "IC3") (pin "48") (pinfunction "(XCK1)PD5_48") (pintype "bidirectional"))
    )
    (net (code "129") (name "unconnected-(IC3-PH2(XCK2)-Pad14)") (class "Default")
      (node (ref "IC3") (pin "14") (pinfunction "PH2(XCK2)_14") (pintype "bidirectional"))
    )
    (net (code "130") (name "unconnected-(IC3-PH7(T4)-Pad27)") (class "Default")
      (node (ref "IC3") (pin "27") (pinfunction "PH7(T4)_27") (pintype "bidirectional"))
    )
    (net (code "131") (name "unconnected-(IC3-PJ2(XCK3{slash}PCINT11)-Pad65)") (class "Default")
      (node (ref "IC3") (pin "65") (pinfunction "PJ2(XCK3/PCINT11)_65") (pintype "bidirectional"))
    )
    (net (code "132") (name "unconnected-(IC3-PJ3(PCINT12)-Pad66)") (class "Default")
      (node (ref "IC3") (pin "66") (pinfunction "PJ3(PCINT12)_66") (pintype "bidirectional"))
    )
    (net (code "133") (name "unconnected-(IC3-PJ4(PCINT13)-Pad67)") (class "Default")
      (node (ref "IC3") (pin "67") (pinfunction "PJ4(PCINT13)_67") (pintype "bidirectional"))
    )
    (net (code "134") (name "unconnected-(IC3-PJ5(PCINT14)-Pad68)") (class "Default")
      (node (ref "IC3") (pin "68") (pinfunction "PJ5(PCINT14)_68") (pintype "bidirectional"))
    )
    (net (code "135") (name "unconnected-(IC3-PJ6(PCINT15)-Pad69)") (class "Default")
      (node (ref "IC3") (pin "69") (pinfunction "PJ6(PCINT15)_69") (pintype "bidirectional"))
    )
    (net (code "136") (name "unconnected-(IC3-PJ7-Pad79)") (class "Default")
      (node (ref "IC3") (pin "79") (pinfunction "PJ7_79") (pintype "bidirectional"))
    )
    (net (code "137") (name "unconnected-(J2-PadRING_SW)") (class "Default")
      (node (ref "J2") (pin "RING_SW") (pinfunction "RING_SW_RING_SW") (pintype "bidirectional"))
    )
    (net (code "138") (name "unconnected-(POWER-Pad1)") (class "Default")
      (node (ref "POWER") (pin "1") (pinfunction "1_1") (pintype "passive"))
    )
    (net (code "139") (name "unconnected-(POWER_SELECT1-Pad1)") (class "Default")
      (node (ref "POWER_SELECT1") (pin "1") (pinfunction "1_1") (pintype "passive"))
    )
    (net (code "140") (name "unconnected-(POWER_SELECT1-Pad2)") (class "Default")
      (node (ref "POWER_SELECT1") (pin "2") (pinfunction "2_2") (pintype "passive"))
    )
    (net (code "141") (name "unconnected-(POWER_SELECT1-Pad3)") (class "Default")
      (node (ref "POWER_SELECT1") (pin "3") (pinfunction "3_3") (pintype "passive"))
    )
    (net (code "142") (name "unconnected-(S2-P-Pad3)") (class "Default")
      (node (ref "S2") (pin "3") (pinfunction "P_3") (pintype "passive"))
    )
    (net (code "143") (name "unconnected-(S2-P1-Pad4)") (class "Default")
      (node (ref "S2") (pin "4") (pinfunction "P1_4") (pintype "passive"))
    )
    (net (code "144") (name "unconnected-(S2-S-Pad1)") (class "Default")
      (node (ref "S2") (pin "1") (pinfunction "S_1") (pintype "passive"))
    )
    (net (code "145") (name "unconnected-(S2-S1-Pad2)") (class "Default")
      (node (ref "S2") (pin "2") (pinfunction "S1_2") (pintype "passive"))
    )
    (net (code "146") (name "unconnected-(XBEE-AD0{slash}DIO0-Pad20)") (class "Default")
      (node (ref "XBEE") (pin "20") (pinfunction "AD0/DIO0_20") (pintype "bidirectional"))
    )
    (net (code "147") (name "unconnected-(XBEE-AD1{slash}DIO1-Pad19)") (class "Default")
      (node (ref "XBEE") (pin "19") (pinfunction "AD1/DIO1_19") (pintype "bidirectional"))
    )
    (net (code "148") (name "unconnected-(XBEE-AD2{slash}DIO2-Pad18)") (class "Default")
      (node (ref "XBEE") (pin "18") (pinfunction "AD2/DIO2_18") (pintype "bidirectional"))
    )
    (net (code "149") (name "unconnected-(XBEE-AD3{slash}DIO3-Pad17)") (class "Default")
      (node (ref "XBEE") (pin "17") (pinfunction "AD3/DIO3_17") (pintype "bidirectional"))
    )
    (net (code "150") (name "unconnected-(XBEE-AD4{slash}DIO4-Pad11)") (class "Default")
      (node (ref "XBEE") (pin "11") (pinfunction "AD4/DIO4_11") (pintype "bidirectional"))
    )
    (net (code "151") (name "unconnected-(XBEE-DO8-Pad4)") (class "Default")
      (node (ref "XBEE") (pin "4") (pinfunction "DO8_4") (pintype "output"))
    )
    (net (code "152") (name "unconnected-(XBEE-ON{slash}SLEEP-Pad13)") (class "Default")
      (node (ref "XBEE") (pin "13") (pinfunction "ON/SLEEP_13") (pintype "output"))
    )
    (net (code "153") (name "unconnected-(XBEE-PWM1-Pad7)") (class "Default")
      (node (ref "XBEE") (pin "7") (pinfunction "PWM1_7") (pintype "output"))
    )
    (net (code "154") (name "unconnected-(XBEE-RESERVED-Pad8)") (class "Default")
      (node (ref "XBEE") (pin "8") (pinfunction "RESERVED_8") (pintype "no_connect"))
    )
    (net (code "155") (name "unconnected-(XBEE-RTS{slash}AD6{slash}DIO6-Pad16)") (class "Default")
      (node (ref "XBEE") (pin "16") (pinfunction "RTS/AD6/DIO6_16") (pintype "bidirectional"))
    )
    (net (code "156") (name "unconnected-(XBEE-VREF-Pad14)") (class "Default")
      (node (ref "XBEE") (pin "14") (pinfunction "VREF_14") (pintype "input"))
    )
  )
)
